# rotary-encoder.net
KiCad netlist of a schematic drawn in Altium Designer
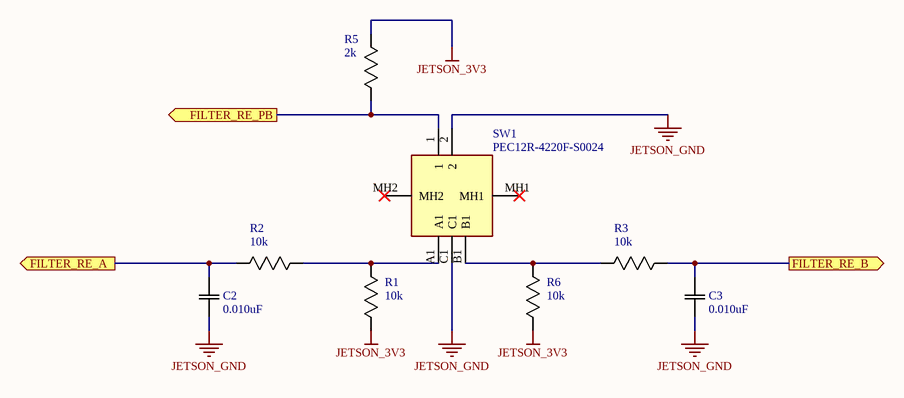
[diagram p0: rotary-encoder.SchDoc]

(export (version "E")
  (design (tool "Eeschema 10.0.6"))
  (components
    (comp (ref "C2")
      (value "0.010uF")
      (footprint "0603")
      (description "CAP CER 0.010UF 16V X5R 0603/0805")
      (fields (field (name "TOLERANCE") "10%") (field (name "PART NUMBER") "CAP 0.010uF 16V"))
      (libsource (lib "Capacitor_Library") (part "CAP 0.010uF 16V"))
    )
    (comp (ref "C3")
      (value "0.010uF")
      (footprint "0603")
      (description "CAP CER 0.010UF 16V X5R 0603/0805")
      (fields (field (name "TOLERANCE") "10%") (field (name "PART NUMBER") "CAP 0.010uF 16V"))
      (libsource (lib "Capacitor_Library") (part "CAP 0.010uF 16V"))
    )
    (comp (ref "R1")
      (value "10k")
      (footprint "0805")
      (description "RES SMD 10K OHM 1% 1/8W 0805")
      (fields (field (name "TOLERANCE") "5%") (field (name "PART NUMBER") "RES 10k 1/8W 1%"))
      (libsource (lib "") (part "RES 10k 1/8W 1%_1"))
    )
    (comp (ref "R2")
      (value "10k")
      (footprint "0805")
      (description "RES SMD 10K OHM 1% 1/8W 0805")
      (fields (field (name "TOLERANCE") "5%") (field (name "PART NUMBER") "RES 10k 1/8W 1%"))
      (libsource (lib "Resistor_Library") (part "RES 10k 1/8W 1%"))
    )
    (comp (ref "R3")
      (value "10k")
      (footprint "0805")
      (description "RES SMD 10K OHM 1% 1/8W 0805")
      (fields (field (name "TOLERANCE") "5%") (field (name "PART NUMBER") "RES 10k 1/8W 1%"))
      (libsource (lib "") (part "RES 10k 1/8W 1%_1"))
    )
    (comp (ref "R5")
      (value "2k")
      (footprint "0603")
      (description "RES SMD 2K OHM 5% 1/8W 0805")
      (fields (field (name "TOLERANCE") "5%") (field (name "PART NUMBER") "RES 2k 1/8W"))
      (libsource (lib "Resistor_Library") (part "RES 2k 1/8W"))
    )
    (comp (ref "R6")
      (value "10k")
      (footprint "0805")
      (description "RES SMD 10K OHM 1% 1/8W 0805")
      (fields (field (name "TOLERANCE") "5%") (field (name "PART NUMBER") "RES 10k 1/8W 1%"))
      (libsource (lib "Resistor_Library") (part "RES 10k 1/8W 1%"))
    )
    (comp (ref "SW1")
      (value "PEC12R-4220F-S0024")
      (footprint "PEC12R4220FS0024")
      (description "Rotary Encoder")
      (fields
        (field (name "MOUSER PART NUMBER") "652-PEC12R-4220F-S24")
        (field (name "PART NUMBER") "PEC12R4220FS0024")
      )
      (libsource (lib "Switch_Library") (part "PEC12R-4220F-S0024"))
    )
  )
  (nets
    (net (code "1") (name "/FILTER_RE_A") (class "Default")
      (node (ref "C2") (pin "2") (pinfunction "C2_2") (pintype "passive"))
      (node (ref "R2") (pin "2") (pinfunction "R2_2") (pintype "passive"))
    )
    (net (code "2") (name "/FILTER_RE_B") (class "Default")
      (node (ref "C3") (pin "2") (pinfunction "C2_2") (pintype "passive"))
      (node (ref "R3") (pin "1") (pinfunction "R1_1") (pintype "passive"))
    )
    (net (code "3") (name "/FILTER_RE_PB") (class "Default")
      (node (ref "R5") (pin "2") (pinfunction "R2_2") (pintype "passive"))
      (node (ref "SW1") (pin "1") (pinfunction "1_1") (pintype "passive"))
    )
    (net (code "4") (name "JETSON_3V3") (class "Default")
      (node (ref "R1") (pin "2") (pinfunction "R2_2") (pintype "passive"))
      (node (ref "R5") (pin "1") (pinfunction "R1_1") (pintype "passive"))
      (node (ref "R6") (pin "2") (pinfunction "R2_2") (pintype "passive"))
    )
    (net (code "5") (name "JETSON_GND") (class "Default")
      (node (ref "C2") (pin "1") (pinfunction "C1_1") (pintype "passive"))
      (node (ref "C3") (pin "1") (pinfunction "C1_1") (pintype "passive"))
      (node (ref "SW1") (pin "2") (pinfunction "2_2") (pintype "passive"))
      (node (ref "SW1") (pin "C1") (pinfunction "C1_C1") (pintype "passive"))
    )
    (net (code "6") (name "Net-(R1-R1)") (class "Default")
      (node (ref "R1") (pin "1") (pinfunction "R1_1") (pintype "passive"))
      (node (ref "R2") (pin "1") (pinfunction "R1_1") (pintype "passive"))
      (node (ref "SW1") (pin "A1") (pinfunction "A1_A1") (pintype "passive"))
    )
    (net (code "7") (name "Net-(R3-R2)") (class "Default")
      (node (ref "R3") (pin "2") (pinfunction "R2_2") (pintype "passive"))
      (node (ref "R6") (pin "1") (pinfunction "R1_1") (pintype "passive"))
      (node (ref "SW1") (pin "B1") (pinfunction "B1_B1") (pintype "passive"))
    )
    (net (code "8") (name "unconnected-(SW1-PadMH1)") (class "Default")
      (node (ref "SW1") (pin "MH1") (pinfunction "MH1_MH1") (pintype "passive+no_connect"))
    )
    (net (code "9") (name "unconnected-(SW1-PadMH2)") (class "Default")
      (node (ref "SW1") (pin "MH2") (pinfunction "MH2_MH2") (pintype "passive+no_connect"))
    )
  )
)
